# 16_BoardPowerSupply.net
KiCad netlist of a schematic drawn in Altium Designer
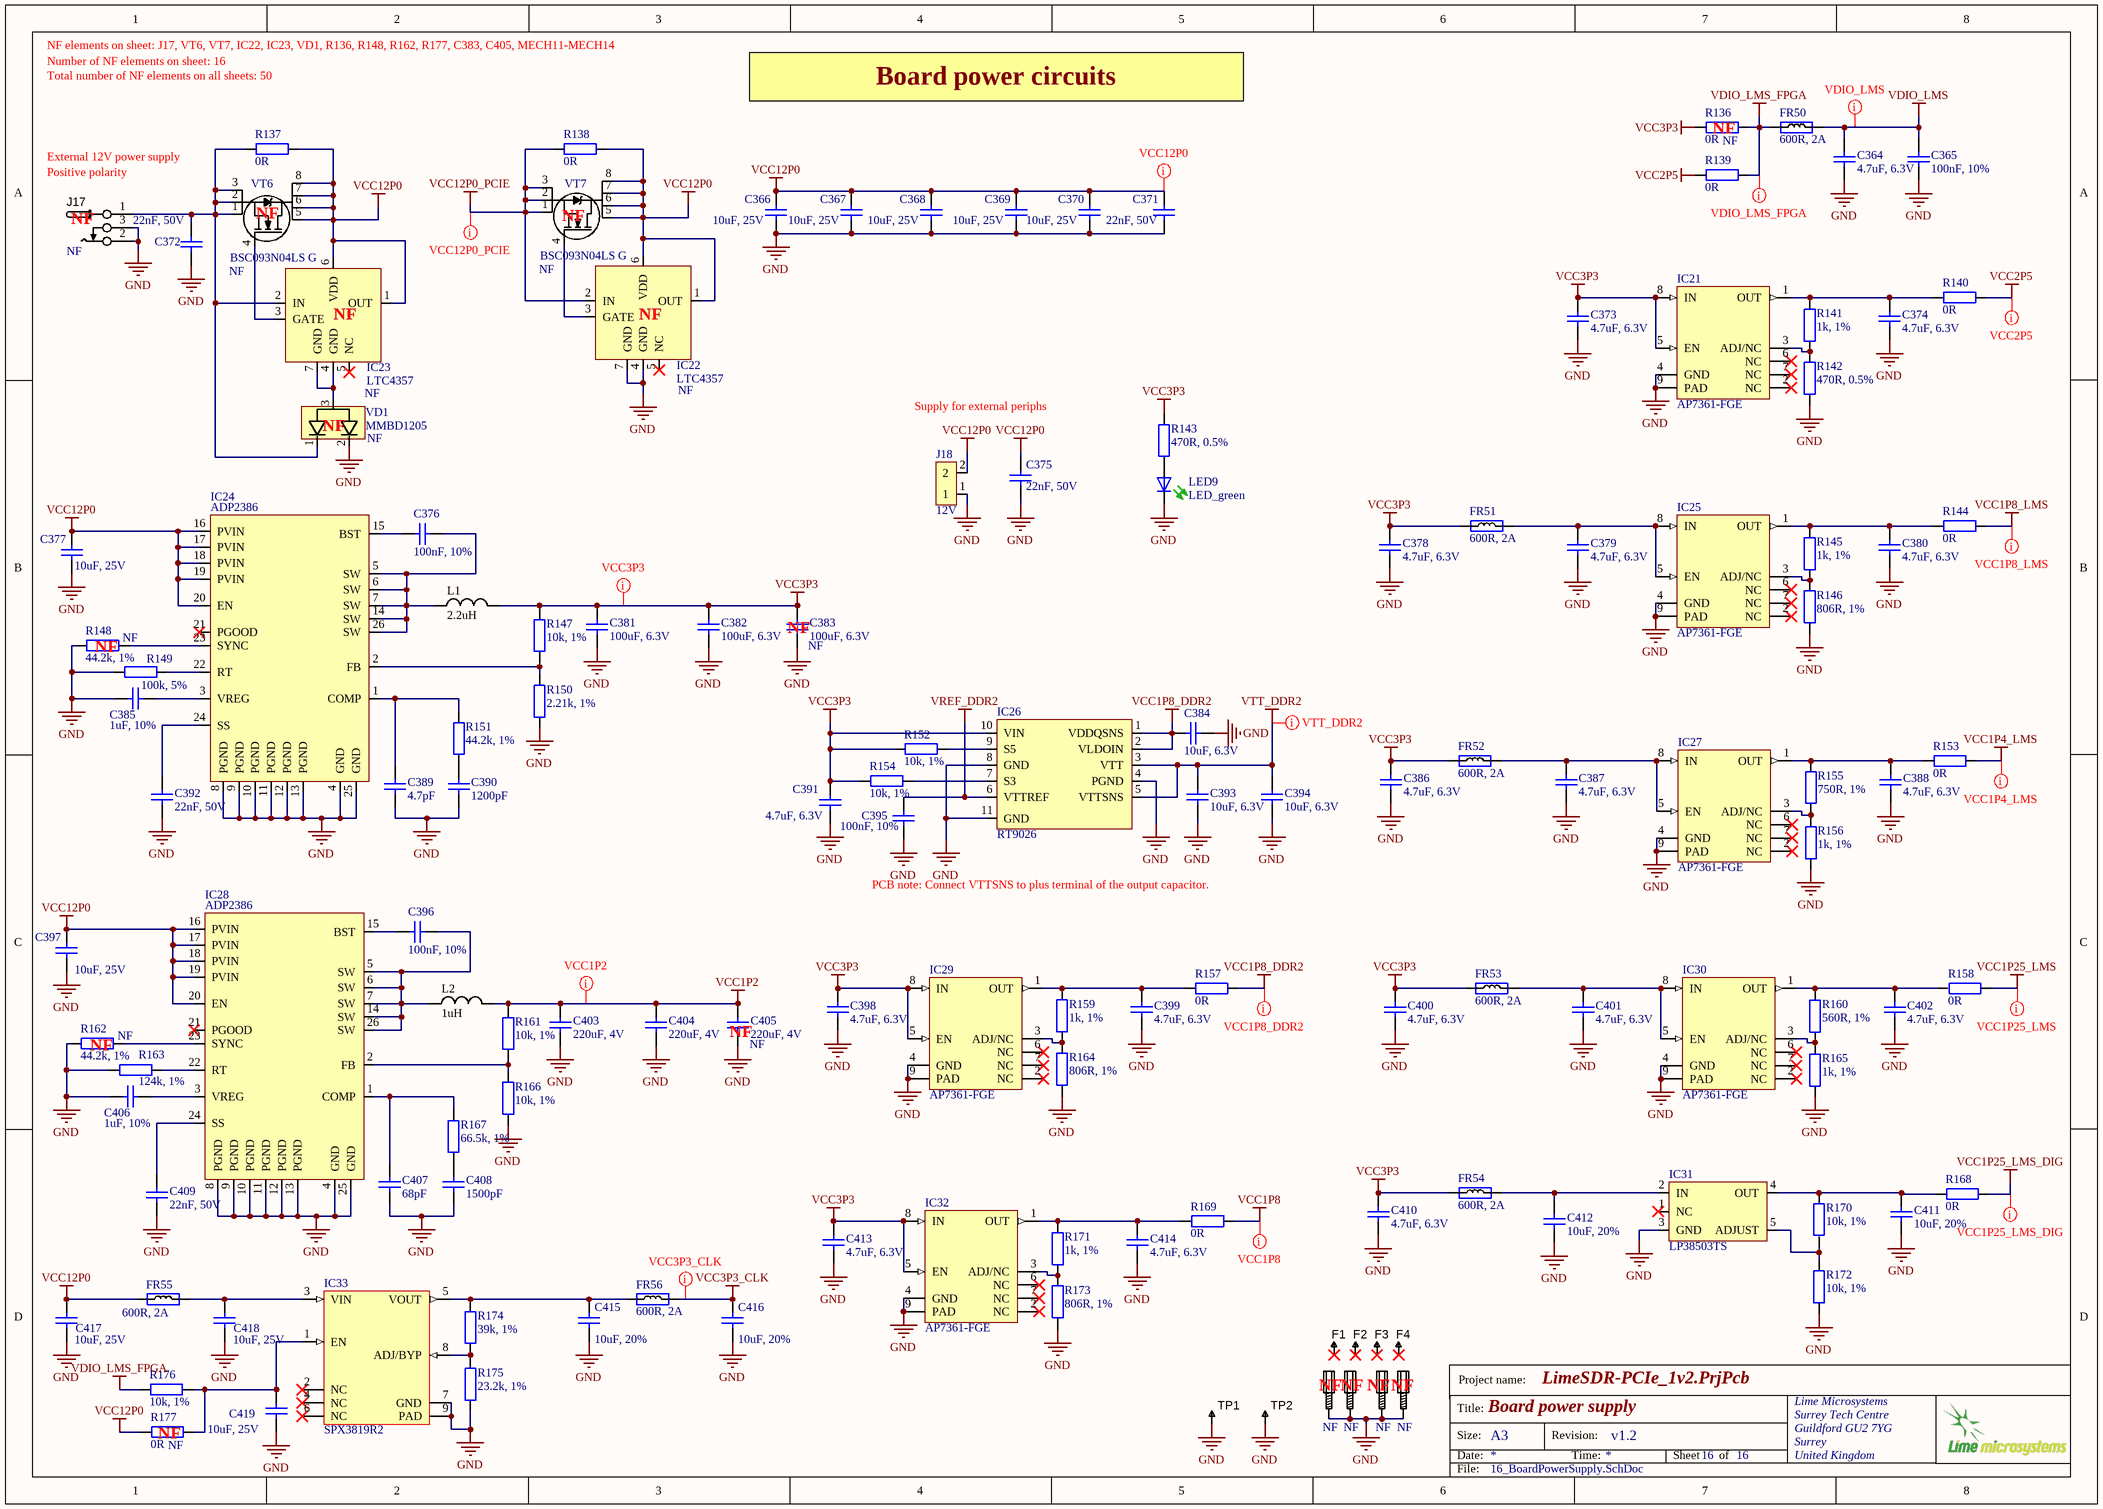
[diagram p0: 16_BoardPowerSupply.SchDoc]

(export (version "E")
  (design (tool "Eeschema 10.0.6"))
  (components
    (comp (ref "C364")
      (value "4.7uF, 6.3V")
      (footprint "CAP0402")
      (fields
        (field (name "MANUFACTURER") "Murata Electronics North America")
        (field (name "TOLERANCE") "±20%")
      )
      (libsource (lib "LimeMicroAltiumLib_schLib") (part "Cap_0402"))
    )
    (comp (ref "C365")
      (value "100nF, 10%")
      (footprint "CAP0402")
      (fields
        (field (name "MANUFACTURER") "Murata Electronics")
        (field (name "TOLERANCE") "10 %")
        (field (name "MANUFACTURER PART NUMBER") "GRM155R71C104KA88D")
      )
      (libsource (lib "LimeMicroAltiumLib_schLib") (part "Cap_0402"))
    )
    (comp (ref "C366")
      (value "10uF, 25V")
      (footprint "CAP0603")
      (fields
        (field (name "MANUFACTURER") "Murata Electronics North America")
        (field (name "MANUFACTURER PART NUMBER") "GRM188R61E106MA73D")
        (field (name "TOLERANCE") "±20%")
      )
      (libsource (lib "LimeMicroAltiumLib_schLib") (part "Cap_0603"))
    )
    (comp (ref "C367")
      (value "10uF, 25V")
      (footprint "CAP0603")
      (fields
        (field (name "MANUFACTURER") "Murata Electronics North America")
        (field (name "MANUFACTURER PART NUMBER") "GRM188R61E106MA73D")
        (field (name "TOLERANCE") "±20%")
      )
      (libsource (lib "LimeMicroAltiumLib_schLib") (part "Cap_0603"))
    )
    (comp (ref "C368")
      (value "10uF, 25V")
      (footprint "CAP0603")
      (fields
        (field (name "MANUFACTURER") "Murata Electronics North America")
        (field (name "MANUFACTURER PART NUMBER") "GRM188R61E106MA73D")
        (field (name "TOLERANCE") "±20%")
      )
      (libsource (lib "LimeMicroAltiumLib_schLib") (part "Cap_0603"))
    )
    (comp (ref "C369")
      (value "10uF, 25V")
      (footprint "CAP0603")
      (fields
        (field (name "MANUFACTURER") "Murata Electronics North America")
        (field (name "MANUFACTURER PART NUMBER") "GRM188R61E106MA73D")
        (field (name "TOLERANCE") "±20%")
      )
      (libsource (lib "LimeMicroAltiumLib_schLib") (part "Cap_0603"))
    )
    (comp (ref "C370")
      (value "10uF, 25V")
      (footprint "CAP0603")
      (fields
        (field (name "MANUFACTURER") "Murata Electronics North America")
        (field (name "MANUFACTURER PART NUMBER") "GRM188R61E106MA73D")
        (field (name "TOLERANCE") "±20%")
      )
      (libsource (lib "LimeMicroAltiumLib_schLib") (part "Cap_0603"))
    )
    (comp (ref "C371")
      (value "22nF, 50V")
      (footprint "CAP0402")
      (fields (field (name "TOLERANCE") "±10%") (field (name "MANUFACTURER") "Kemet"))
      (libsource (lib "LimeMicroAltiumLib_schLib") (part "Cap_0402"))
    )
    (comp (ref "C372")
      (value "22nF, 50V")
      (footprint "CAP0402")
      (fields (field (name "TOLERANCE") "±10%") (field (name "MANUFACTURER") "Kemet"))
      (libsource (lib "LimeMicroAltiumLib_schLib") (part "Cap_0402"))
    )
    (comp (ref "C373")
      (value "4.7uF, 6.3V")
      (footprint "CAP0402")
      (fields
        (field (name "MANUFACTURER") "Murata Electronics North America")
        (field (name "TOLERANCE") "±20%")
      )
      (libsource (lib "LimeMicroAltiumLib_schLib") (part "Cap_0402"))
    )
    (comp (ref "C374")
      (value "4.7uF, 6.3V")
      (footprint "CAP0402")
      (fields
        (field (name "MANUFACTURER") "Murata Electronics North America")
        (field (name "TOLERANCE") "±20%")
      )
      (libsource (lib "LimeMicroAltiumLib_schLib") (part "Cap_0402"))
    )
    (comp (ref "C375")
      (value "22nF, 50V")
      (footprint "CAP0402")
      (fields (field (name "TOLERANCE") "±10%") (field (name "MANUFACTURER") "Kemet"))
      (libsource (lib "LimeMicroAltiumLib_schLib") (part "Cap_0402"))
    )
    (comp (ref "C376")
      (value "100nF, 10%")
      (footprint "CAP0402")
      (fields
        (field (name "MANUFACTURER") "Murata Electronics")
        (field (name "TOLERANCE") "10 %")
        (field (name "MANUFACTURER PART NUMBER") "GRM155R71C104KA88D")
      )
      (libsource (lib "LimeMicroAltiumLib_schLib") (part "Cap_0402"))
    )
    (comp (ref "C377")
      (value "10uF, 25V")
      (footprint "CAP0603")
      (fields
        (field (name "MANUFACTURER") "Murata Electronics North America")
        (field (name "MANUFACTURER PART NUMBER") "GRM188R61E106MA73D")
        (field (name "TOLERANCE") "±20%")
      )
      (libsource (lib "LimeMicroAltiumLib_schLib") (part "Cap_0603"))
    )
    (comp (ref "C378")
      (value "4.7uF, 6.3V")
      (footprint "CAP0402")
      (fields
        (field (name "MANUFACTURER") "Murata Electronics North America")
        (field (name "TOLERANCE") "±20%")
      )
      (libsource (lib "LimeMicroAltiumLib_schLib") (part "Cap_0402"))
    )
    (comp (ref "C379")
      (value "4.7uF, 6.3V")
      (footprint "CAP0402")
      (fields
        (field (name "MANUFACTURER") "Murata Electronics North America")
        (field (name "TOLERANCE") "±20%")
      )
      (libsource (lib "LimeMicroAltiumLib_schLib") (part "Cap_0402"))
    )
    (comp (ref "C380")
      (value "4.7uF, 6.3V")
      (footprint "CAP0402")
      (fields
        (field (name "MANUFACTURER") "Murata Electronics North America")
        (field (name "TOLERANCE") "±20%")
      )
      (libsource (lib "LimeMicroAltiumLib_schLib") (part "Cap_0402"))
    )
    (comp (ref "C381")
      (value "100uF, 6.3V")
      (footprint "CAP1206")
      (fields (field (name "MANUFACTURER") "MURATA"))
      (libsource (lib "LimeFPGAboard_schLib") (part "Cap_1206"))
    )
    (comp (ref "C382")
      (value "100uF, 6.3V")
      (footprint "CAP1206")
      (fields (field (name "MANUFACTURER") "MURATA"))
      (libsource (lib "LimeFPGAboard_schLib") (part "Cap_1206"))
    )
    (comp (ref "C383")
      (value "100uF, 6.3V")
      (footprint "CAP1206")
      (fields (field (name "MANUFACTURER") "MURATA") (field (name "ASSEMBLY INFO") "NF"))
      (libsource (lib "LimeFPGAboard_schLib") (part "Cap_1206"))
    )
    (comp (ref "C384")
      (value "10uF, 6.3V")
      (footprint "CAP0603")
      (fields (field (name "TOLERANCE") "±20%") (field (name "MANUFACTURER") "Yageo"))
      (libsource (lib "LimeFPGAboard_schLib") (part "Cap_0603"))
    )
    (comp (ref "C385")
      (value "1uF, 10%")
      (footprint "CAP0402")
      (fields (field (name "MANUFACTURER") "TDK"))
      (libsource (lib "LimeMicroAltiumLib_schLib") (part "Cap_0402"))
    )
    (comp (ref "C386")
      (value "4.7uF, 6.3V")
      (footprint "CAP0402")
      (fields
        (field (name "MANUFACTURER") "Murata Electronics North America")
        (field (name "TOLERANCE") "±20%")
      )
      (libsource (lib "LimeMicroAltiumLib_schLib") (part "Cap_0402"))
    )
    (comp (ref "C387")
      (value "4.7uF, 6.3V")
      (footprint "CAP0402")
      (fields
        (field (name "MANUFACTURER") "Murata Electronics North America")
        (field (name "TOLERANCE") "±20%")
      )
      (libsource (lib "LimeMicroAltiumLib_schLib") (part "Cap_0402"))
    )
    (comp (ref "C388")
      (value "4.7uF, 6.3V")
      (footprint "CAP0402")
      (fields
        (field (name "MANUFACTURER") "Murata Electronics North America")
        (field (name "TOLERANCE") "±20%")
      )
      (libsource (lib "LimeMicroAltiumLib_schLib") (part "Cap_0402"))
    )
    (comp (ref "C389")
      (value "4.7pF")
      (footprint "CAP0402")
      (fields (field (name "MANUFACTURER") "MURATA"))
      (libsource (lib "LimeMicroAltiumLib_schLib") (part "Cap_0402"))
    )
    (comp (ref "C390")
      (value "1200pF")
      (footprint "CAP0402")
      (fields (field (name "MANUFACTURER") "Kemet") (field (name "TOLERANCE") "±5%"))
      (libsource (lib "LimeMicroAltiumLib_schLib") (part "Cap_0402"))
    )
    (comp (ref "C391")
      (value "4.7uF, 6.3V")
      (footprint "CAP0402")
      (fields
        (field (name "MANUFACTURER") "Murata Electronics North America")
        (field (name "TOLERANCE") "±20%")
      )
      (libsource (lib "LimeMicroAltiumLib_schLib") (part "Cap_0402"))
    )
    (comp (ref "C392")
      (value "22nF, 50V")
      (footprint "CAP0402")
      (fields (field (name "TOLERANCE") "±10%") (field (name "MANUFACTURER") "Kemet"))
      (libsource (lib "LimeMicroAltiumLib_schLib") (part "Cap_0402"))
    )
    (comp (ref "C393")
      (value "10uF, 6.3V")
      (footprint "CAP0603")
      (fields (field (name "TOLERANCE") "±20%") (field (name "MANUFACTURER") "Yageo"))
      (libsource (lib "LimeFPGAboard_schLib") (part "Cap_0603"))
    )
    (comp (ref "C394")
      (value "10uF, 6.3V")
      (footprint "CAP0603")
      (fields (field (name "TOLERANCE") "±20%") (field (name "MANUFACTURER") "Yageo"))
      (libsource (lib "LimeFPGAboard_schLib") (part "Cap_0603"))
    )
    (comp (ref "C395")
      (value "100nF, 10%")
      (footprint "CAP0402")
      (fields
        (field (name "MANUFACTURER") "Murata Electronics")
        (field (name "TOLERANCE") "10 %")
        (field (name "MANUFACTURER PART NUMBER") "GRM155R71C104KA88D")
      )
      (libsource (lib "LimeMicroAltiumLib_schLib") (part "Cap_0402"))
    )
    (comp (ref "C396")
      (value "100nF, 10%")
      (footprint "CAP0402")
      (fields
        (field (name "MANUFACTURER") "Murata Electronics")
        (field (name "TOLERANCE") "10 %")
        (field (name "MANUFACTURER PART NUMBER") "GRM155R71C104KA88D")
      )
      (libsource (lib "LimeMicroAltiumLib_schLib") (part "Cap_0402"))
    )
    (comp (ref "C397")
      (value "10uF, 25V")
      (footprint "CAP0603")
      (fields
        (field (name "MANUFACTURER") "Murata Electronics North America")
        (field (name "MANUFACTURER PART NUMBER") "GRM188R61E106MA73D")
        (field (name "TOLERANCE") "±20%")
      )
      (libsource (lib "LimeMicroAltiumLib_schLib") (part "Cap_0603"))
    )
    (comp (ref "C398")
      (value "4.7uF, 6.3V")
      (footprint "CAP0402")
      (fields
        (field (name "MANUFACTURER") "Murata Electronics North America")
        (field (name "TOLERANCE") "±20%")
      )
      (libsource (lib "LimeMicroAltiumLib_schLib") (part "Cap_0402"))
    )
    (comp (ref "C399")
      (value "4.7uF, 6.3V")
      (footprint "CAP0402")
      (fields
        (field (name "MANUFACTURER") "Murata Electronics North America")
        (field (name "TOLERANCE") "±20%")
      )
      (libsource (lib "LimeMicroAltiumLib_schLib") (part "Cap_0402"))
    )
    (comp (ref "C400")
      (value "4.7uF, 6.3V")
      (footprint "CAP0402")
      (fields
        (field (name "MANUFACTURER") "Murata Electronics North America")
        (field (name "TOLERANCE") "±20%")
      )
      (libsource (lib "LimeMicroAltiumLib_schLib") (part "Cap_0402"))
    )
    (comp (ref "C401")
      (value "4.7uF, 6.3V")
      (footprint "CAP0402")
      (fields
        (field (name "MANUFACTURER") "Murata Electronics North America")
        (field (name "TOLERANCE") "±20%")
      )
      (libsource (lib "LimeMicroAltiumLib_schLib") (part "Cap_0402"))
    )
    (comp (ref "C402")
      (value "4.7uF, 6.3V")
      (footprint "CAP0402")
      (fields
        (field (name "MANUFACTURER") "Murata Electronics North America")
        (field (name "TOLERANCE") "±20%")
      )
      (libsource (lib "LimeMicroAltiumLib_schLib") (part "Cap_0402"))
    )
    (comp (ref "C403")
      (value "220uF, 4V")
      (footprint "CAP1206")
      (fields
        (field (name "MANUFACTURER PART NUMBER") "GRM31CR60G227ME11L")
        (field (name "MANUFACTURER") "Murata Electronics North America")
        (field (name "TOLERANCE") "±20%")
      )
      (libsource (lib "LimeFPGAboard_schLib") (part "Cap_1206"))
    )
    (comp (ref "C404")
      (value "220uF, 4V")
      (footprint "CAP1206")
      (fields
        (field (name "MANUFACTURER PART NUMBER") "GRM31CR60G227ME11L")
        (field (name "MANUFACTURER") "Murata Electronics North America")
        (field (name "TOLERANCE") "±20%")
      )
      (libsource (lib "LimeFPGAboard_schLib") (part "Cap_1206"))
    )
    (comp (ref "C405")
      (value "220uF, 4V")
      (footprint "CAP1206")
      (fields
        (field (name "MANUFACTURER PART NUMBER") "GRM31CR60G227ME11L")
        (field (name "MANUFACTURER") "Murata Electronics North America")
        (field (name "TOLERANCE") "±20%")
        (field (name "ASSEMBLY INFO") "NF")
      )
      (libsource (lib "LimeFPGAboard_schLib") (part "Cap_1206"))
    )
    (comp (ref "C406")
      (value "1uF, 10%")
      (footprint "CAP0402")
      (fields (field (name "MANUFACTURER") "TDK"))
      (libsource (lib "LimeMicroAltiumLib_schLib") (part "Cap_0402"))
    )
    (comp (ref "C407")
      (value "68pF")
      (footprint "CAP0402")
      (fields (field (name "TOLERANCE") "±1%") (field (name "MANUFACTURER") "Kemet"))
      (libsource (lib "LimeMicroAltiumLib_schLib") (part "Cap_0402"))
    )
    (comp (ref "C408")
      (value "1500pF")
      (footprint "CAP0402")
      (fields
        (field (name "MANUFACTURER") "Samsung Electro-Mechanics America, Inc.")
        (field (name "TOLERANCE") "±10%")
      )
      (libsource (lib "LimeMicroAltiumLib_schLib") (part "Cap_0402"))
    )
    (comp (ref "C409")
      (value "22nF, 50V")
      (footprint "CAP0402")
      (fields (field (name "TOLERANCE") "±10%") (field (name "MANUFACTURER") "Kemet"))
      (libsource (lib "LimeMicroAltiumLib_schLib") (part "Cap_0402"))
    )
    (comp (ref "C410")
      (value "4.7uF, 6.3V")
      (footprint "CAP0402")
      (fields
        (field (name "MANUFACTURER") "Murata Electronics North America")
        (field (name "TOLERANCE") "±20%")
      )
      (libsource (lib "LimeMicroAltiumLib_schLib") (part "Cap_0402"))
    )
    (comp (ref "C411")
      (value "10uF, 20%")
      (footprint "CAP0603")
      (fields (field (name "MANUFACTURER") "Yageo") (field (name "TOLERANCE") "±20%"))
      (libsource (lib "LimeMicroAltiumLib_schLib") (part "Cap_0603"))
    )
    (comp (ref "C412")
      (value "10uF, 20%")
      (footprint "CAP0603")
      (fields (field (name "MANUFACTURER") "Yageo") (field (name "TOLERANCE") "±20%"))
      (libsource (lib "LimeMicroAltiumLib_schLib") (part "Cap_0603"))
    )
    (comp (ref "C413")
      (value "4.7uF, 6.3V")
      (footprint "CAP0402")
      (fields
        (field (name "MANUFACTURER") "Murata Electronics North America")
        (field (name "TOLERANCE") "±20%")
      )
      (libsource (lib "LimeMicroAltiumLib_schLib") (part "Cap_0402"))
    )
    (comp (ref "C414")
      (value "4.7uF, 6.3V")
      (footprint "CAP0402")
      (fields
        (field (name "MANUFACTURER") "Murata Electronics North America")
        (field (name "TOLERANCE") "±20%")
      )
      (libsource (lib "LimeMicroAltiumLib_schLib") (part "Cap_0402"))
    )
    (comp (ref "C415")
      (value "10uF, 20%")
      (footprint "CAP0603")
      (fields (field (name "MANUFACTURER") "Yageo") (field (name "TOLERANCE") "±20%"))
      (libsource (lib "LimeMicroAltiumLib_schLib") (part "Cap_0603"))
    )
    (comp (ref "C416")
      (value "10uF, 20%")
      (footprint "CAP0603")
      (fields (field (name "MANUFACTURER") "Yageo") (field (name "TOLERANCE") "±20%"))
      (libsource (lib "LimeMicroAltiumLib_schLib") (part "Cap_0603"))
    )
    (comp (ref "C417")
      (value "10uF, 25V")
      (footprint "CAP0603")
      (fields
        (field (name "MANUFACTURER") "Murata Electronics North America")
        (field (name "MANUFACTURER PART NUMBER") "GRM188R61E106MA73D")
        (field (name "TOLERANCE") "±20%")
      )
      (libsource (lib "LimeMicroAltiumLib_schLib") (part "Cap_0603"))
    )
    (comp (ref "C418")
      (value "10uF, 25V")
      (footprint "CAP0603")
      (fields
        (field (name "MANUFACTURER") "Murata Electronics North America")
        (field (name "MANUFACTURER PART NUMBER") "GRM188R61E106MA73D")
        (field (name "TOLERANCE") "±20%")
      )
      (libsource (lib "LimeMicroAltiumLib_schLib") (part "Cap_0603"))
    )
    (comp (ref "C419")
      (value "10uF, 25V")
      (footprint "CAP0603")
      (fields
        (field (name "MANUFACTURER") "Murata Electronics North America")
        (field (name "MANUFACTURER PART NUMBER") "GRM188R61E106MA73D")
        (field (name "TOLERANCE") "±20%")
      )
      (libsource (lib "LimeMicroAltiumLib_schLib") (part "Cap_0603"))
    )
    (comp (ref "F1")
      (value "Fiducial")
      (footprint "Fiducial")
      (libsource (lib "LimeMicroAltiumLib_schLib") (part "Fiducial"))
    )
    (comp (ref "F2")
      (value "Fiducial")
      (footprint "Fiducial")
      (libsource (lib "LimeMicroAltiumLib_schLib") (part "Fiducial"))
    )
    (comp (ref "F3")
      (value "Fiducial")
      (footprint "Fiducial")
      (libsource (lib "LimeMicroAltiumLib_schLib") (part "Fiducial"))
    )
    (comp (ref "F4")
      (value "Fiducial")
      (footprint "Fiducial")
      (libsource (lib "LimeMicroAltiumLib_schLib") (part "Fiducial"))
    )
    (comp (ref "FR50")
      (value "600R, 2A")
      (footprint "RES0805")
      (fields (field (name "MANUFACTURER") "TDK Corporation"))
      (libsource (lib "LimeMicroAltiumLib_schLib") (part "Ferrite"))
    )
    (comp (ref "FR51")
      (value "600R, 2A")
      (footprint "RES0805")
      (fields (field (name "MANUFACTURER") "TDK Corporation"))
      (libsource (lib "LimeMicroAltiumLib_schLib") (part "Ferrite"))
    )
    (comp (ref "FR52")
      (value "600R, 2A")
      (footprint "RES0805")
      (fields (field (name "MANUFACTURER") "TDK Corporation"))
      (libsource (lib "LimeMicroAltiumLib_schLib") (part "Ferrite"))
    )
    (comp (ref "FR53")
      (value "600R, 2A")
      (footprint "RES0805")
      (fields (field (name "MANUFACTURER") "TDK Corporation"))
      (libsource (lib "LimeMicroAltiumLib_schLib") (part "Ferrite"))
    )
    (comp (ref "FR54")
      (value "600R, 2A")
      (footprint "RES0805")
      (fields (field (name "MANUFACTURER") "TDK Corporation"))
      (libsource (lib "LimeMicroAltiumLib_schLib") (part "Ferrite"))
    )
    (comp (ref "FR55")
      (value "600R, 2A")
      (footprint "RES0805")
      (fields (field (name "MANUFACTURER") "TDK Corporation"))
      (libsource (lib "LimeMicroAltiumLib_schLib") (part "Ferrite"))
    )
    (comp (ref "FR56")
      (value "600R, 2A")
      (footprint "RES0805")
      (fields (field (name "MANUFACTURER") "TDK Corporation"))
      (libsource (lib "LimeMicroAltiumLib_schLib") (part "Ferrite"))
    )
    (comp (ref "IC21")
      (value "AP7361-FGE")
      (footprint "AP7361")
      (fields
        (field (name "MANUFACTURER PART NUMBER") "AP7361-FGE-7")
        (field (name "MANUFACTURER") "Diodes Incorporated")
      )
      (libsource (lib "LimeMicroAltiumLib_schLib") (part "AP7361"))
    )
    (comp (ref "IC22")
      (value "LTC4357")
      (footprint "LTC4357")
      (fields
        (field (name "MANUFACTURER PART NUMBER") "LTC4357IDCB#TRMPBF")
        (field (name "MANUFACTURER") "Linear Technology")
        (field (name "ASSEMBLY INFO") "NF")
      )
      (libsource (lib "LimeFPGAboard_schLib") (part "LTC4357"))
    )
    (comp (ref "IC23")
      (value "LTC4357")
      (footprint "LTC4357")
      (fields
        (field (name "MANUFACTURER PART NUMBER") "LTC4357IDCB#TRMPBF")
        (field (name "MANUFACTURER") "Linear Technology")
        (field (name "ASSEMBLY INFO") "NF")
      )
      (libsource (lib "LimeFPGAboard_schLib") (part "LTC4357"))
    )
    (comp (ref "IC24")
      (value "ADP2386")
      (footprint "ADP2386")
      (fields
        (field (name "MANUFACTURER PART NUMBER") "ADP2386ACPZN-R7")
        (field (name "MANUFACTURER") "Analog Devices Inc.")
      )
      (libsource (lib "LimeMicroAltiumLib_schLib") (part "ADP2386"))
    )
    (comp (ref "IC25")
      (value "AP7361-FGE")
      (footprint "AP7361")
      (fields
        (field (name "MANUFACTURER PART NUMBER") "AP7361-FGE-7")
        (field (name "MANUFACTURER") "Diodes Incorporated")
      )
      (libsource (lib "LimeMicroAltiumLib_schLib") (part "AP7361"))
    )
    (comp (ref "IC26")
      (value "RT9026")
      (footprint "MSOP10")
      (fields (field (name "MANUFACTURER") "Richtek USA Inc."))
      (libsource (lib "LimeMicroAltiumLib_schLib") (part "RT9026"))
    )
    (comp (ref "IC27")
      (value "AP7361-FGE")
      (footprint "AP7361")
      (fields
        (field (name "MANUFACTURER PART NUMBER") "AP7361-FGE-7")
        (field (name "MANUFACTURER") "Diodes Incorporated")
      )
      (libsource (lib "LimeMicroAltiumLib_schLib") (part "AP7361"))
    )
    (comp (ref "IC28")
      (value "ADP2386")
      (footprint "ADP2386")
      (fields (field (name "MANUFACTURER") "Analog Devices Inc."))
      (libsource (lib "LimeMicroAltiumLib_schLib") (part "ADP2386"))
    )
    (comp (ref "IC29")
      (value "AP7361-FGE")
      (footprint "AP7361")
      (fields
        (field (name "MANUFACTURER PART NUMBER") "AP7361-FGE-7")
        (field (name "MANUFACTURER") "Diodes Incorporated")
      )
      (libsource (lib "LimeMicroAltiumLib_schLib") (part "AP7361"))
    )
    (comp (ref "IC30")
      (value "AP7361-FGE")
      (footprint "AP7361")
      (fields
        (field (name "MANUFACTURER PART NUMBER") "AP7361-FGE-7")
        (field (name "MANUFACTURER") "Diodes Incorporated")
      )
      (libsource (lib "LimeMicroAltiumLib_schLib") (part "AP7361"))
    )
    (comp (ref "IC31")
      (value "LP38503TS")
      (footprint "TO-263-5_v2")
      (fields
        (field (name "MANUFACTURER PART NUMBER") "LP38503TS-ADJ/NOPB")
        (field (name "MANUFACTURER") "Texas Instruments")
      )
      (libsource (lib "LimeMicroAltiumLib_schLib") (part "LP38503TS"))
    )
    (comp (ref "IC32")
      (value "AP7361-FGE")
      (footprint "AP7361")
      (fields
        (field (name "MANUFACTURER PART NUMBER") "AP7361-FGE-7")
        (field (name "MANUFACTURER") "Diodes Incorporated")
      )
      (libsource (lib "LimeMicroAltiumLib_schLib") (part "AP7361"))
    )
    (comp (ref "IC33")
      (value "SPX3819R2")
      (footprint "SPX3819R2-L/TR")
      (fields (field (name "MANUFACTURER") "Exar Corporation"))
      (libsource (lib "LimeMicroAltiumLib_schLib") (part "SPX3819R2-L/TR"))
    )
    (comp (ref "J17")
      (value "CONN_PWR_JACK_2.1x5.5mm")
      (footprint "CONN_PWR_JACK_v2")
      (description "Power Connector, THT, 2.1mm ID, 5.5mm OD")
      (fields (field (name "MANUFACTURER") "SWITCHCRAFT") (field (name "ASSEMBLY INFO") "NF"))
      (libsource (lib "LimeFPGAboard_schLib") (part "CONN_PWR_JACK_2.1x5.5mm"))
    )
    (comp (ref "J18")
      (value "12V")
      (footprint "HDR_1x2")
      (fields (field (name "MANUFACTURER") "3M"))
      (libsource (lib "LimeFPGAboard_schLib") (part "Jumper"))
    )
    (comp (ref "L1")
      (value "2.2uH")
      (footprint "FDVE1040_TOKO_INDUCTOR")
      (fields (field (name "TOLERANCE") "±20%") (field (name "MANUFACTURER") "Vishay Dale"))
      (libsource (lib "LimeMicroAltiumLib_schLib") (part "Inductor_0603"))
    )
    (comp (ref "L2")
      (value "1uH")
      (footprint "FDVE1040_TOKO_INDUCTOR")
      (fields (field (name "TOLERANCE") "±20%") (field (name "MANUFACTURER") "Vishay Dale"))
      (libsource (lib "LimeMicroAltiumLib_schLib") (part "Inductor_0603"))
    )
    (comp (ref "LED9")
      (value "LED_green")
      (footprint "LED-0603-GREEN")
      (fields (field (name "MANUFACTURER") "Broadcom Limited"))
      (libsource (lib "LimeFPGAboard_schLib") (part "LED_green"))
    )
    (comp (ref "MECH11")
      (value "# pcs.")
      (footprint "PCB_standoff")
      (description "STANDOFF M/F MET 5MM HEX 10MM L")
      (fields (field (name "MANUFACTURER") "Keystone Electronics") (field (name "ASSEMBLY INFO") "NF"))
      (libsource (lib "LimeMicroAltiumLib_schLib") (part "STANDOFF_M-F_THREADED_M3x8x10mm_HEX_5mm dia"))
    )
    (comp (ref "MECH12")
      (value "# pcs.")
      (footprint "PCB_standoff")
      (description "STANDOFF M/F MET 5MM HEX 10MM L")
      (fields (field (name "MANUFACTURER") "Keystone Electronics") (field (name "ASSEMBLY INFO") "NF"))
      (libsource (lib "LimeMicroAltiumLib_schLib") (part "STANDOFF_M-F_THREADED_M3x8x10mm_HEX_5mm dia"))
    )
    (comp (ref "MECH13")
      (value "# pcs.")
      (footprint "PCB_standoff")
      (description "STANDOFF M/F MET 5MM HEX 10MM L")
      (fields (field (name "MANUFACTURER") "Keystone Electronics") (field (name "ASSEMBLY INFO") "NF"))
      (libsource (lib "LimeMicroAltiumLib_schLib") (part "STANDOFF_M-F_THREADED_M3x8x10mm_HEX_5mm dia"))
    )
    (comp (ref "MECH14")
      (value "# pcs.")
      (footprint "PCB_standoff")
      (description "STANDOFF M/F MET 5MM HEX 10MM L")
      (fields (field (name "MANUFACTURER") "Keystone Electronics") (field (name "ASSEMBLY INFO") "NF"))
      (libsource (lib "LimeMicroAltiumLib_schLib") (part "STANDOFF_M-F_THREADED_M3x8x10mm_HEX_5mm dia"))
    )
    (comp (ref "R136")
      (value "0R")
      (footprint "RES0402")
      (fields
        (field (name "ASSEMBLY INFO") "NF")
        (field (name "MANUFACTURER") "Yageo")
        (field (name "TOLERANCE") "Jumper")
      )
      (libsource (lib "LimeMicroAltiumLib_schLib") (part "Res_0402"))
    )
    (comp (ref "R137")
      (value "0R")
      (footprint "RES0805")
      (fields (field (name "MANUFACTURER") "Vishay Dale") (field (name "TOLERANCE") "Jumper"))
      (libsource (lib "LimeMicroAltiumLib_schLib") (part "Res_0402"))
    )
    (comp (ref "R138")
      (value "0R")
      (footprint "RES0805")
      (fields (field (name "MANUFACTURER") "Vishay Dale") (field (name "TOLERANCE") "Jumper"))
      (libsource (lib "LimeMicroAltiumLib_schLib") (part "Res_0402"))
    )
    (comp (ref "R139")
      (value "0R")
      (footprint "RES0402")
      (fields (field (name "MANUFACTURER") "Yageo") (field (name "TOLERANCE") "Jumper"))
      (libsource (lib "LimeMicroAltiumLib_schLib") (part "Res_0402"))
    )
    (comp (ref "R140")
      (value "0R")
      (footprint "RES0402")
      (fields (field (name "MANUFACTURER") "Yageo") (field (name "TOLERANCE") "Jumper"))
      (libsource (lib "LimeMicroAltiumLib_schLib") (part "Res_0402"))
    )
    (comp (ref "R141")
      (value "1k, 1%")
      (footprint "RES0402")
      (fields (field (name "MANUFACTURER") "Stackpole Electronics Inc") (field (name "TOLERANCE") "±1%"))
      (libsource (lib "LimeMicroAltiumLib_schLib") (part "Res_0402"))
    )
    (comp (ref "R142")
      (value "470R, 0.5%")
      (footprint "RES0402")
      (fields
        (field (name "TOLERANCE") "±0.5%")
        (field (name "MANUFACTURER") "Panasonic Electronic Components")
      )
      (libsource (lib "LimeMicroAltiumLib_schLib") (part "Res_0402"))
    )
    (comp (ref "R143")
      (value "470R, 0.5%")
      (footprint "RES0402")
      (fields (field (name "TOLERANCE") "±0.5%"))
      (libsource (lib "LimeFPGAboard_schLib") (part "Res_0402"))
    )
    (comp (ref "R144")
      (value "0R")
      (footprint "RES0402")
      (fields (field (name "MANUFACTURER") "Yageo") (field (name "TOLERANCE") "Jumper"))
      (libsource (lib "LimeMicroAltiumLib_schLib") (part "Res_0402"))
    )
    (comp (ref "R145")
      (value "1k, 1%")
      (footprint "RES0402")
      (fields (field (name "MANUFACTURER") "Stackpole Electronics Inc") (field (name "TOLERANCE") "±1%"))
      (libsource (lib "LimeMicroAltiumLib_schLib") (part "Res_0402"))
    )
    (comp (ref "R146")
      (value "806R, 1%")
      (footprint "RES0402")
      (fields (field (name "TOLERANCE") "±1%") (field (name "MANUFACTURER") "Stackpole Electronics Inc"))
      (libsource (lib "LimeMicroAltiumLib_schLib") (part "Res_0402"))
    )
    (comp (ref "R147")
      (value "10k, 1%")
      (footprint "RES0402")
      (fields (field (name "MANUFACTURER") "Yageo") (field (name "TOLERANCE") "±1%"))
      (libsource (lib "LimeMicroAltiumLib_schLib") (part "Res_0402"))
    )
    (comp (ref "R148")
      (value "44.2k, 1%")
      (footprint "RES0402")
      (fields
        (field (name "ASSEMBLY INFO") "NF")
        (field (name "TOLERANCE") "±1%")
        (field (name "MANUFACTURER") "Panasonic Electronic Components")
      )
      (libsource (lib "LimeMicroAltiumLib_schLib") (part "Res_0402"))
    )
    (comp (ref "R149")
      (value "100k, 5%")
      (footprint "RES0402")
      (fields
        (field (name "MANUFACTURER") "Panasonic Electronic Components")
        (field (name "MANUFACTURER PART NUMBER") "ERJ-2GEJ104X")
        (field (name "TOLERANCE") "±5%")
      )
      (libsource (lib "LimeMicroAltiumLib_schLib") (part "Res_0402"))
    )
    (comp (ref "R150")
      (value "2.21k, 1%")
      (footprint "RES0402")
      (fields (field (name "MANUFACTURER") "Stackpole Electronics Inc.") (field (name "TOLERANCE") "±1%"))
      (libsource (lib "LimeMicroAltiumLib_schLib") (part "Res_0402"))
    )
    (comp (ref "R151")
      (value "44.2k, 1%")
      (footprint "RES0402")
      (fields
        (field (name "TOLERANCE") "±1%")
        (field (name "MANUFACTURER") "Panasonic Electronic Components")
      )
      (libsource (lib "LimeMicroAltiumLib_schLib") (part "Res_0402"))
    )
    (comp (ref "R152")
      (value "10k, 1%")
      (footprint "RES0402")
      (fields (field (name "MANUFACTURER") "Yageo") (field (name "TOLERANCE") "±1%"))
      (libsource (lib "LimeMicroAltiumLib_schLib") (part "Res_0402"))
    )
    (comp (ref "R153")
      (value "0R")
      (footprint "RES0402")
      (fields (field (name "MANUFACTURER") "Yageo") (field (name "TOLERANCE") "Jumper"))
      (libsource (lib "LimeMicroAltiumLib_schLib") (part "Res_0402"))
    )
    (comp (ref "R154")
      (value "10k, 1%")
      (footprint "RES0402")
      (fields (field (name "MANUFACTURER") "Yageo") (field (name "TOLERANCE") "±1%"))
      (libsource (lib "LimeMicroAltiumLib_schLib") (part "Res_0402"))
    )
    (comp (ref "R155")
      (value "750R, 1%")
      (footprint "RES0402")
      (fields
        (field (name "TOLERANCE") "±1%")
        (field (name "MANUFACTURER PART NUMBER") "RC0402FR-07750RL")
        (field (name "MANUFACTURER") "Yageo")
      )
      (libsource (lib "LimeMicroAltiumLib_schLib") (part "Res_0402"))
    )
    (comp (ref "R156")
      (value "1k, 1%")
      (footprint "RES0402")
      (fields (field (name "MANUFACTURER") "Stackpole Electronics Inc") (field (name "TOLERANCE") "±1%"))
      (libsource (lib "LimeMicroAltiumLib_schLib") (part "Res_0402"))
    )
    (comp (ref "R157")
      (value "0R")
      (footprint "RES0402")
      (fields (field (name "MANUFACTURER") "Yageo") (field (name "TOLERANCE") "Jumper"))
      (libsource (lib "LimeMicroAltiumLib_schLib") (part "Res_0402"))
    )
    (comp (ref "R158")
      (value "0R")
      (footprint "RES0402")
      (fields (field (name "MANUFACTURER") "Yageo") (field (name "TOLERANCE") "Jumper"))
      (libsource (lib "LimeMicroAltiumLib_schLib") (part "Res_0402"))
    )
    (comp (ref "R159")
      (value "1k, 1%")
      (footprint "RES0402")
      (fields (field (name "MANUFACTURER") "Stackpole Electronics Inc") (field (name "TOLERANCE") "±1%"))
      (libsource (lib "LimeMicroAltiumLib_schLib") (part "Res_0402"))
    )
    (comp (ref "R160")
      (value "560R, 1%")
      (footprint "RES0402")
      (fields
        (field (name "MANUFACTURER PART NUMBER") "CRCW0402560RFKED")
        (field (name "TOLERANCE") "±1%")
        (field (name "MANUFACTURER") "Vishay Dale")
      )
      (libsource (lib "LimeMicroAltiumLib_schLib") (part "Res_0402"))
    )
    (comp (ref "R161")
      (value "10k, 1%")
      (footprint "RES0402")
      (fields (field (name "MANUFACTURER") "Yageo") (field (name "TOLERANCE") "±1%"))
      (libsource (lib "LimeMicroAltiumLib_schLib") (part "Res_0402"))
    )
    (comp (ref "R162")
      (value "44.2k, 1%")
      (footprint "RES0402")
      (fields
        (field (name "ASSEMBLY INFO") "NF")
        (field (name "TOLERANCE") "±1%")
        (field (name "MANUFACTURER") "Panasonic Electronic Components")
      )
      (libsource (lib "LimeMicroAltiumLib_schLib") (part "Res_0402"))
    )
    (comp (ref "R163")
      (value "124k, 1%")
      (footprint "RES0402")
      (fields
        (field (name "MANUFACTURER") "Panasonic Electronic Components")
        (field (name "TOLERANCE") "±1%")
      )
      (libsource (lib "LimeMicroAltiumLib_schLib") (part "Res_0402"))
    )
    (comp (ref "R164")
      (value "806R, 1%")
      (footprint "RES0402")
      (fields (field (name "TOLERANCE") "±1%") (field (name "MANUFACTURER") "Stackpole Electronics Inc"))
      (libsource (lib "LimeMicroAltiumLib_schLib") (part "Res_0402"))
    )
    (comp (ref "R165")
      (value "1k, 1%")
      (footprint "RES0402")
      (fields (field (name "MANUFACTURER") "Stackpole Electronics Inc") (field (name "TOLERANCE") "±1%"))
      (libsource (lib "LimeMicroAltiumLib_schLib") (part "Res_0402"))
    )
    (comp (ref "R166")
      (value "10k, 1%")
      (footprint "RES0402")
      (fields (field (name "MANUFACTURER") "Yageo") (field (name "TOLERANCE") "±1%"))
      (libsource (lib "LimeMicroAltiumLib_schLib") (part "Res_0402"))
    )
    (comp (ref "R167")
      (value "66.5k, 1%")
      (footprint "RES0402")
      (fields
        (field (name "MANUFACTURER") "Panasonic Electronic Components")
        (field (name "TOLERANCE") "±1%")
      )
      (libsource (lib "LimeMicroAltiumLib_schLib") (part "Res_0402"))
    )
    (comp (ref "R168")
      (value "0R")
      (footprint "RES0402")
      (fields (field (name "MANUFACTURER") "Yageo") (field (name "TOLERANCE") "Jumper"))
      (libsource (lib "LimeMicroAltiumLib_schLib") (part "Res_0402"))
    )
    (comp (ref "R169")
      (value "0R")
      (footprint "RES0402")
      (fields (field (name "MANUFACTURER") "Yageo") (field (name "TOLERANCE") "Jumper"))
      (libsource (lib "LimeMicroAltiumLib_schLib") (part "Res_0402"))
    )
    (comp (ref "R170")
      (value "10k, 1%")
      (footprint "RES0402")
      (fields (field (name "MANUFACTURER") "Yageo") (field (name "TOLERANCE") "±1%"))
      (libsource (lib "LimeMicroAltiumLib_schLib") (part "Res_0402"))
    )
    (comp (ref "R171")
      (value "1k, 1%")
      (footprint "RES0402")
      (fields (field (name "MANUFACTURER") "Stackpole Electronics Inc") (field (name "TOLERANCE") "±1%"))
      (libsource (lib "LimeMicroAltiumLib_schLib") (part "Res_0402"))
    )
    (comp (ref "R172")
      (value "10k, 1%")
      (footprint "RES0402")
      (fields (field (name "MANUFACTURER") "Yageo") (field (name "TOLERANCE") "±1%"))
      (libsource (lib "LimeMicroAltiumLib_schLib") (part "Res_0402"))
    )
    (comp (ref "R173")
      (value "806R, 1%")
      (footprint "RES0402")
      (fields (field (name "TOLERANCE") "±1%") (field (name "MANUFACTURER") "Stackpole Electronics Inc"))
      (libsource (lib "LimeMicroAltiumLib_schLib") (part "Res_0402"))
    )
    (comp (ref "R174")
      (value "39k, 1%")
      (footprint "RES0402")
      (fields (field (name "MANUFACTURER") "Yageo") (field (name "TOLERANCE") "±1%"))
      (libsource (lib "LimeMicroAltiumLib_schLib") (part "Res_0402"))
    )
    (comp (ref "R175")
      (value "23.2k, 1%")
      (footprint "RES0402")
      (fields (field (name "TOLERANCE") "±1%") (field (name "MANUFACTURER") "Yageo"))
      (libsource (lib "LimeMicroAltiumLib_schLib") (part "Res_0402"))
    )
    (comp (ref "R176")
      (value "10k, 1%")
      (footprint "RES0402")
      (fields (field (name "MANUFACTURER") "Yageo") (field (name "TOLERANCE") "±1%"))
      (libsource (lib "LimeMicroAltiumLib_schLib") (part "Res_0402"))
    )
    (comp (ref "R177")
      (value "0R")
      (footprint "RES0402")
      (fields
        (field (name "ASSEMBLY INFO") "NF")
        (field (name "MANUFACTURER") "Yageo")
        (field (name "TOLERANCE") "Jumper")
      )
      (libsource (lib "LimeMicroAltiumLib_schLib") (part "Res_0402"))
    )
    (comp (ref "TP1")
      (value "TESTPOINT_THT_MINI")
      (footprint "TP-THT-MIDI")
      (description "Test Point PCB mount Miniature White")
      (fields (field (name "MANUFACTURER") "Keystone Electronics"))
      (libsource (lib "LimeMicroAltiumLib_schLib") (part "TESTPOINT_THT_MINI"))
    )
    (comp (ref "TP2")
      (value "TESTPOINT_THT_MINI")
      (footprint "TP-THT-MIDI")
      (description "Test Point PCB mount Miniature White")
      (fields (field (name "MANUFACTURER") "Keystone Electronics"))
      (libsource (lib "LimeMicroAltiumLib_schLib") (part "TESTPOINT_THT_MINI"))
    )
    (comp (ref "VD1")
      (value "MMBD1205")
      (footprint "SOT23-3_v2")
      (fields (field (name "MANUFACTURER") "FAIRCHILD SEMICONDUCTOR") (field (name "ASSEMBLY INFO") "NF"))
      (libsource (lib "LimeFPGAboard_schLib") (part "MMBD1205"))
    )
    (comp (ref "VT6")
      (value "BSC093N04LS G")
      (footprint "BSC093N04LS_G")
      (fields (field (name "MANUFACTURER") "Infineon Technologies") (field (name "ASSEMBLY INFO") "NF"))
      (libsource (lib "LimeFPGAboard_schLib") (part "BSC093N04LS_G"))
    )
    (comp (ref "VT7")
      (value "BSC093N04LS G")
      (footprint "BSC093N04LS_G")
      (fields (field (name "MANUFACTURER") "Infineon Technologies") (field (name "ASSEMBLY INFO") "NF"))
      (libsource (lib "LimeFPGAboard_schLib") (part "BSC093N04LS_G"))
    )
  )
  (nets
    (net (code "1") (name "GND") (class "Default")
      (node (ref "C364") (pin "1") (pinfunction "1_1") (pintype "passive"))
      (node (ref "C365") (pin "2") (pinfunction "2_2") (pintype "passive"))
      (node (ref "C366") (pin "1") (pinfunction "1_1") (pintype "passive"))
      (node (ref "C367") (pin "1") (pinfunction "1_1") (pintype "passive"))
      (node (ref "C368") (pin "1") (pinfunction "1_1") (pintype "passive"))
      (node (ref "C369") (pin "1") (pinfunction "1_1") (pintype "passive"))
      (node (ref "C370") (pin "1") (pinfunction "1_1") (pintype "passive"))
      (node (ref "C371") (pin "2") (pinfunction "2_2") (pintype "passive"))
      (node (ref "C372") (pin "2") (pinfunction "2_2") (pintype "passive"))
      (node (ref "C373") (pin "1") (pinfunction "1_1") (pintype "passive"))
      (node (ref "C374") (pin "1") (pinfunction "1_1") (pintype "passive"))
      (node (ref "C375") (pin "2") (pinfunction "2_2") (pintype "passive"))
      (node (ref "C377") (pin "1") (pinfunction "1_1") (pintype "passive"))
      (node (ref "C378") (pin "1") (pinfunction "1_1") (pintype "passive"))
      (node (ref "C379") (pin "1") (pinfunction "1_1") (pintype "passive"))
      (node (ref "C380") (pin "1") (pinfunction "1_1") (pintype "passive"))
      (node (ref "C381") (pin "1") (pinfunction "1_1") (pintype "passive"))
      (node (ref "C382") (pin "1") (pinfunction "1_1") (pintype "passive"))
      (node (ref "C383") (pin "1") (pinfunction "1_1") (pintype "passive"))
      (node (ref "C384") (pin "1") (pinfunction "1_1") (pintype "passive"))
      (node (ref "C385") (pin "2") (pinfunction "2_2") (pintype "passive"))
      (node (ref "C386") (pin "1") (pinfunction "1_1") (pintype "passive"))
      (node (ref "C387") (pin "1") (pinfunction "1_1") (pintype "passive"))
      (node (ref "C388") (pin "1") (pinfunction "1_1") (pintype "passive"))
      (node (ref "C389") (pin "2") (pinfunction "2_2") (pintype "passive"))
      (node (ref "C390") (pin "2") (pinfunction "2_2") (pintype "passive"))
      (node (ref "C391") (pin "1") (pinfunction "1_1") (pintype "passive"))
      (node (ref "C392") (pin "2") (pinfunction "2_2") (pintype "passive"))
      (node (ref "C393") (pin "1") (pinfunction "1_1") (pintype "passive"))
      (node (ref "C394") (pin "1") (pinfunction "1_1") (pintype "passive"))
      (node (ref "C395") (pin "2") (pinfunction "2_2") (pintype "passive"))
      (node (ref "C397") (pin "1") (pinfunction "1_1") (pintype "passive"))
      (node (ref "C398") (pin "1") (pinfunction "1_1") (pintype "passive"))
      (node (ref "C399") (pin "1") (pinfunction "1_1") (pintype "passive"))
      (node (ref "C400") (pin "1") (pinfunction "1_1") (pintype "passive"))
      (node (ref "C401") (pin "1") (pinfunction "1_1") (pintype "passive"))
      (node (ref "C402") (pin "1") (pinfunction "1_1") (pintype "passive"))
      (node (ref "C403") (pin "1") (pinfunction "1_1") (pintype "passive"))
      (node (ref "C404") (pin "1") (pinfunction "1_1") (pintype "passive"))
      (node (ref "C405") (pin "1") (pinfunction "1_1") (pintype "passive"))
      (node (ref "C406") (pin "2") (pinfunction "2_2") (pintype "passive"))
      (node (ref "C407") (pin "2") (pinfunction "2_2") (pintype "passive"))
      (node (ref "C408") (pin "2") (pinfunction "2_2") (pintype "passive"))
      (node (ref "C409") (pin "2") (pinfunction "2_2") (pintype "passive"))
      (node (ref "C410") (pin "1") (pinfunction "1_1") (pintype "passive"))
      (node (ref "C411") (pin "1") (pinfunction "1_1") (pintype "passive"))
      (node (ref "C412") (pin "1") (pinfunction "1_1") (pintype "passive"))
      (node (ref "C413") (pin "1") (pinfunction "1_1") (pintype "passive"))
      (node (ref "C414") (pin "1") (pinfunction "1_1") (pintype "passive"))
      (node (ref "C415") (pin "1") (pinfunction "1_1") (pintype "passive"))
      (node (ref "C416") (pin "1") (pinfunction "1_1") (pintype "passive"))
      (node (ref "C417") (pin "1") (pinfunction "1_1") (pintype "passive"))
      (node (ref "C418") (pin "1") (pinfunction "1_1") (pintype "passive"))
      (node (ref "C419") (pin "1") (pinfunction "1_1") (pintype "passive"))
      (node (ref "IC21") (pin "4") (pinfunction "GND_4") (pintype "passive"))
      (node (ref "IC21") (pin "9") (pinfunction "PAD_9") (pintype "passive"))
      (node (ref "IC22") (pin "4") (pinfunction "GND_4") (pintype "passive"))
      (node (ref "IC22") (pin "7") (pinfunction "GND_7") (pintype "passive"))
      (node (ref "IC24") (pin "10") (pinfunction "PGND_10") (pintype "passive"))
      (node (ref "IC24") (pin "11") (pinfunction "PGND_11") (pintype "passive"))
      (node (ref "IC24") (pin "12") (pinfunction "PGND_12") (pintype "passive"))
      (node (ref "IC24") (pin "13") (pinfunction "PGND_13") (pintype "passive"))
      (node (ref "IC24") (pin "25") (pinfunction "GND_25") (pintype "passive"))
      (node (ref "IC24") (pin "4") (pinfunction "GND_4") (pintype "passive"))
      (node (ref "IC24") (pin "8") (pinfunction "PGND_8") (pintype "passive"))
      (node (ref "IC24") (pin "9") (pinfunction "PGND_9") (pintype "passive"))
      (node (ref "IC25") (pin "4") (pinfunction "GND_4") (pintype "passive"))
      (node (ref "IC25") (pin "9") (pinfunction "PAD_9") (pintype "passive"))
      (node (ref "IC26") (pin "11") (pinfunction "GND_11") (pintype "passive"))
      (node (ref "IC26") (pin "4") (pinfunction "PGND_4") (pintype "passive"))
      (node (ref "IC26") (pin "8") (pinfunction "GND_8") (pintype "passive"))
      (node (ref "IC27") (pin "4") (pinfunction "GND_4") (pintype "passive"))
      (node (ref "IC27") (pin "9") (pinfunction "PAD_9") (pintype "passive"))
      (node (ref "IC28") (pin "10") (pinfunction "PGND_10") (pintype "passive"))
      (node (ref "IC28") (pin "11") (pinfunction "PGND_11") (pintype "passive"))
      (node (ref "IC28") (pin "12") (pinfunction "PGND_12") (pintype "passive"))
      (node (ref "IC28") (pin "13") (pinfunction "PGND_13") (pintype "passive"))
      (node (ref "IC28") (pin "25") (pinfunction "GND_25") (pintype "passive"))
      (node (ref "IC28") (pin "4") (pinfunction "GND_4") (pintype "passive"))
      (node (ref "IC28") (pin "8") (pinfunction "PGND_8") (pintype "passive"))
      (node (ref "IC28") (pin "9") (pinfunction "PGND_9") (pintype "passive"))
      (node (ref "IC29") (pin "4") (pinfunction "GND_4") (pintype "passive"))
      (node (ref "IC29") (pin "9") (pinfunction "PAD_9") (pintype "passive"))
      (node (ref "IC30") (pin "4") (pinfunction "GND_4") (pintype "passive"))
      (node (ref "IC30") (pin "9") (pinfunction "PAD_9") (pintype "passive"))
      (node (ref "IC31") (pin "3") (pinfunction "GND_3") (pintype "passive"))
      (node (ref "IC32") (pin "4") (pinfunction "GND_4") (pintype "passive"))
      (node (ref "IC32") (pin "9") (pinfunction "PAD_9") (pintype "passive"))
      (node (ref "IC33") (pin "7") (pinfunction "GND_7") (pintype "passive"))
      (node (ref "IC33") (pin "9") (pinfunction "PAD_9") (pintype "passive"))
      (node (ref "J17") (pin "2") (pinfunction "2_2") (pintype "passive"))
      (node (ref "J17") (pin "3") (pinfunction "3_3") (pintype "passive"))
      (node (ref "J18") (pin "1") (pinfunction "1_1") (pintype "passive"))
      (node (ref "LED9") (pin "K") (pinfunction "C_K") (pintype "power_in"))
      (node (ref "MECH11") (pin "MH1") (pinfunction "MH1_MH1") (pintype "passive"))
      (node (ref "MECH12") (pin "MH1") (pinfunction "MH1_MH1") (pintype "passive"))
      (node (ref "MECH13") (pin "MH1") (pinfunction "MH1_MH1") (pintype "passive"))
      (node (ref "MECH14") (pin "MH1") (pinfunction "MH1_MH1") (pintype "passive"))
      (node (ref "R142") (pin "2") (pinfunction "2_2") (pintype "passive"))
      (node (ref "R146") (pin "2") (pinfunction "2_2") (pintype "passive"))
      (node (ref "R148") (pin "1") (pinfunction "1_1") (pintype "passive"))
      (node (ref "R149") (pin "2") (pinfunction "2_2") (pintype "passive"))
      (node (ref "R150") (pin "1") (pinfunction "1_1") (pintype "passive"))
      (node (ref "R156") (pin "1") (pinfunction "1_1") (pintype "passive"))
      (node (ref "R162") (pin "1") (pinfunction "1_1") (pintype "passive"))
      (node (ref "R163") (pin "2") (pinfunction "2_2") (pintype "passive"))
      (node (ref "R164") (pin "2") (pinfunction "2_2") (pintype "passive"))
      (node (ref "R165") (pin "1") (pinfunction "1_1") (pintype "passive"))
      (node (ref "R166") (pin "2") (pinfunction "2_2") (pintype "passive"))
      (node (ref "R172") (pin "2") (pinfunction "2_2") (pintype "passive"))
      (node (ref "R173") (pin "2") (pinfunction "2_2") (pintype "passive"))
      (node (ref "R175") (pin "1") (pinfunction "1_1") (pintype "passive"))
      (node (ref "TP1") (pin "1") (pintype "passive"))
      (node (ref "TP2") (pin "1") (pintype "passive"))
      (node (ref "VD1") (pin "2") (pinfunction "2_2") (pintype "passive"))
    )
    (net (code "2") (name "Net-(C376-Pad2)") (class "Default")
      (node (ref "C376") (pin "2") (pinfunction "2_2") (pintype "passive"))
      (node (ref "IC24") (pin "14") (pinfunction "SW_14") (pintype "passive"))
      (node (ref "IC24") (pin "26") (pinfunction "SW_26") (pintype "passive"))
      (node (ref "IC24") (pin "5") (pinfunction "SW_5") (pintype "passive"))
      (node (ref "IC24") (pin "6") (pinfunction "SW_6") (pintype "passive"))
      (node (ref "IC24") (pin "7") (pinfunction "SW_7") (pintype "passive"))
      (node (ref "L1") (pin "1") (pinfunction "1_1") (pintype "passive"))
    )
    (net (code "3") (name "Net-(C390-Pad1)") (class "Default")
      (node (ref "C390") (pin "1") (pinfunction "1_1") (pintype "passive"))
      (node (ref "R151") (pin "1") (pinfunction "1_1") (pintype "passive"))
    )
    (net (code "4") (name "Net-(C396-Pad2)") (class "Default")
      (node (ref "C396") (pin "2") (pinfunction "2_2") (pintype "passive"))
      (node (ref "IC28") (pin "14") (pinfunction "SW_14") (pintype "passive"))
      (node (ref "IC28") (pin "26") (pinfunction "SW_26") (pintype "passive"))
      (node (ref "IC28") (pin "5") (pinfunction "SW_5") (pintype "passive"))
      (node (ref "IC28") (pin "6") (pinfunction "SW_6") (pintype "passive"))
      (node (ref "IC28") (pin "7") (pinfunction "SW_7") (pintype "passive"))
      (node (ref "L2") (pin "1") (pinfunction "1_1") (pintype "passive"))
    )
    (net (code "5") (name "Net-(C408-Pad1)") (class "Default")
      (node (ref "C408") (pin "1") (pinfunction "1_1") (pintype "passive"))
      (node (ref "R167") (pin "1") (pinfunction "1_1") (pintype "passive"))
    )
    (net (code "6") (name "Net-(IC21-ADJ{slash}NC)") (class "Default")
      (node (ref "IC21") (pin "3") (pinfunction "ADJ/NC_3") (pintype "passive"))
      (node (ref "R141") (pin "1") (pinfunction "1_1") (pintype "passive"))
      (node (ref "R142") (pin "1") (pinfunction "1_1") (pintype "passive"))
    )
    (net (code "7") (name "Net-(IC21-OUT)") (class "Default")
      (node (ref "C374") (pin "2") (pinfunction "2_2") (pintype "passive"))
      (node (ref "IC21") (pin "1") (pinfunction "OUT_1") (pintype "output"))
      (node (ref "R140") (pin "2") (pinfunction "2_2") (pintype "passive"))
      (node (ref "R141") (pin "2") (pinfunction "2_2") (pintype "passive"))
    )
    (net (code "8") (name "Net-(IC22-GATE)") (class "Default")
      (node (ref "IC22") (pin "3") (pinfunction "GATE_3") (pintype "passive"))
      (node (ref "VT7") (pin "4") (pinfunction "G_4") (pintype "passive"))
    )
    (net (code "9") (name "Net-(IC23-GATE)") (class "Default")
      (node (ref "IC23") (pin "3") (pinfunction "GATE_3") (pintype "passive"))
      (node (ref "VT6") (pin "4") (pinfunction "G_4") (pintype "passive"))
    )
    (net (code "10") (name "Net-(IC23-GND-Pad4)") (class "Default")
      (node (ref "IC23") (pin "4") (pinfunction "GND_4") (pintype "passive"))
      (node (ref "IC23") (pin "7") (pinfunction "GND_7") (pintype "passive"))
      (node (ref "VD1") (pin "3") (pinfunction "3_3") (pintype "passive"))
    )
    (net (code "11") (name "Net-(IC23-IN)") (class "Default")
      (node (ref "C372") (pin "1") (pinfunction "1_1") (pintype "passive"))
      (node (ref "IC23") (pin "2") (pinfunction "IN_2") (pintype "passive"))
      (node (ref "J17") (pin "1") (pinfunction "1_1") (pintype "passive"))
      (node (ref "R137") (pin "2") (pinfunction "2_2") (pintype "passive"))
      (node (ref "VD1") (pin "1") (pinfunction "1_1") (pintype "passive"))
      (node (ref "VT6") (pin "1") (pinfunction "S_1") (pintype "passive"))
      (node (ref "VT6") (pin "2") (pinfunction "S_2") (pintype "passive"))
      (node (ref "VT6") (pin "3") (pinfunction "S_3") (pintype "passive"))
    )
    (net (code "12") (name "Net-(IC24-BST)") (class "Default")
      (node (ref "C376") (pin "1") (pinfunction "1_1") (pintype "passive"))
      (node (ref "IC24") (pin "15") (pinfunction "BST_15") (pintype "passive"))
    )
    (net (code "13") (name "Net-(IC24-COMP)") (class "Default")
      (node (ref "C389") (pin "1") (pinfunction "1_1") (pintype "passive"))
      (node (ref "IC24") (pin "1") (pinfunction "COMP_1") (pintype "passive"))
      (node (ref "R151") (pin "2") (pinfunction "2_2") (pintype "passive"))
    )
    (net (code "14") (name "Net-(IC24-FB)") (class "Default")
      (node (ref "IC24") (pin "2") (pinfunction "FB_2") (pintype "passive"))
      (node (ref "R147") (pin "2") (pinfunction "2_2") (pintype "passive"))
      (node (ref "R150") (pin "2") (pinfunction "2_2") (pintype "passive"))
    )
    (net (code "15") (name "Net-(IC24-RT)") (class "Default")
      (node (ref "IC24") (pin "22") (pinfunction "RT_22") (pintype "passive"))
      (node (ref "R149") (pin "1") (pinfunction "1_1") (pintype "passive"))
    )
    (net (code "16") (name "Net-(IC24-SS)") (class "Default")
      (node (ref "C392") (pin "1") (pinfunction "1_1") (pintype "passive"))
      (node (ref "IC24") (pin "24") (pinfunction "SS_24") (pintype "passive"))
    )
    (net (code "17") (name "Net-(IC24-SYNC)") (class "Default")
      (node (ref "IC24") (pin "23") (pinfunction "SYNC_23") (pintype "passive"))
      (node (ref "R148") (pin "2") (pinfunction "2_2") (pintype "passive"))
    )
    (net (code "18") (name "Net-(IC24-VREG)") (class "Default")
      (node (ref "C385") (pin "1") (pinfunction "1_1") (pintype "passive"))
      (node (ref "IC24") (pin "3") (pinfunction "VREG_3") (pintype "passive"))
    )
    (net (code "19") (name "Net-(IC25-ADJ{slash}NC)") (class "Default")
      (node (ref "IC25") (pin "3") (pinfunction "ADJ/NC_3") (pintype "passive"))
      (node (ref "R145") (pin "1") (pinfunction "1_1") (pintype "passive"))
      (node (ref "R146") (pin "1") (pinfunction "1_1") (pintype "passive"))
    )
    (net (code "20") (name "Net-(IC25-EN)") (class "Default")
      (node (ref "C379") (pin "2") (pinfunction "2_2") (pintype "passive"))
      (node (ref "FR51") (pin "2") (pinfunction "2_2") (pintype "passive"))
      (node (ref "IC25") (pin "5") (pinfunction "EN_5") (pintype "input"))
      (node (ref "IC25") (pin "8") (pinfunction "IN_8") (pintype "input"))
    )
    (net (code "21") (name "Net-(IC25-OUT)") (class "Default")
      (node (ref "C380") (pin "2") (pinfunction "2_2") (pintype "passive"))
      (node (ref "IC25") (pin "1") (pinfunction "OUT_1") (pintype "output"))
      (node (ref "R144") (pin "2") (pinfunction "2_2") (pintype "passive"))
      (node (ref "R145") (pin "2") (pinfunction "2_2") (pintype "passive"))
    )
    (net (code "22") (name "Net-(IC26-S3)") (class "Default")
      (node (ref "IC26") (pin "7") (pinfunction "S3_7") (pintype "passive"))
      (node (ref "R154") (pin "2") (pinfunction "2_2") (pintype "passive"))
    )
    (net (code "23") (name "Net-(IC26-S5)") (class "Default")
      (node (ref "IC26") (pin "9") (pinfunction "S5_9") (pintype "passive"))
      (node (ref "R152") (pin "2") (pinfunction "2_2") (pintype "passive"))
    )
    (net (code "24") (name "Net-(IC27-ADJ{slash}NC)") (class "Default")
      (node (ref "IC27") (pin "3") (pinfunction "ADJ/NC_3") (pintype "passive"))
      (node (ref "R155") (pin "2") (pinfunction "2_2") (pintype "passive"))
      (node (ref "R156") (pin "2") (pinfunction "2_2") (pintype "passive"))
    )
    (net (code "25") (name "Net-(IC27-EN)") (class "Default")
      (node (ref "C387") (pin "2") (pinfunction "2_2") (pintype "passive"))
      (node (ref "FR52") (pin "2") (pinfunction "2_2") (pintype "passive"))
      (node (ref "IC27") (pin "5") (pinfunction "EN_5") (pintype "input"))
      (node (ref "IC27") (pin "8") (pinfunction "IN_8") (pintype "input"))
    )
    (net (code "26") (name "Net-(IC27-OUT)") (class "Default")
      (node (ref "C388") (pin "2") (pinfunction "2_2") (pintype "passive"))
      (node (ref "IC27") (pin "1") (pinfunction "OUT_1") (pintype "output"))
      (node (ref "R153") (pin "2") (pinfunction "2_2") (pintype "passive"))
      (node (ref "R155") (pin "1") (pinfunction "1_1") (pintype "passive"))
    )
    (net (code "27") (name "Net-(IC28-BST)") (class "Default")
      (node (ref "C396") (pin "1") (pinfunction "1_1") (pintype "passive"))
      (node (ref "IC28") (pin "15") (pinfunction "BST_15") (pintype "passive"))
    )
    (net (code "28") (name "Net-(IC28-COMP)") (class "Default")
      (node (ref "C407") (pin "1") (pinfunction "1_1") (pintype "passive"))
      (node (ref "IC28") (pin "1") (pinfunction "COMP_1") (pintype "passive"))
      (node (ref "R167") (pin "2") (pinfunction "2_2") (pintype "passive"))
    )
    (net (code "29") (name "Net-(IC28-FB)") (class "Default")
      (node (ref "IC28") (pin "2") (pinfunction "FB_2") (pintype "passive"))
      (node (ref "R161") (pin "2") (pinfunction "2_2") (pintype "passive"))
      (node (ref "R166") (pin "1") (pinfunction "1_1") (pintype "passive"))
    )
    (net (code "30") (name "Net-(IC28-RT)") (class "Default")
      (node (ref "IC28") (pin "22") (pinfunction "RT_22") (pintype "passive"))
      (node (ref "R163") (pin "1") (pinfunction "1_1") (pintype "passive"))
    )
    (net (code "31") (name "Net-(IC28-SS)") (class "Default")
      (node (ref "C409") (pin "1") (pinfunction "1_1") (pintype "passive"))
      (node (ref "IC28") (pin "24") (pinfunction "SS_24") (pintype "passive"))
    )
    (net (code "32") (name "Net-(IC28-SYNC)") (class "Default")
      (node (ref "IC28") (pin "23") (pinfunction "SYNC_23") (pintype "passive"))
      (node (ref "R162") (pin "2") (pinfunction "2_2") (pintype "passive"))
    )
    (net (code "33") (name "Net-(IC28-VREG)") (class "Default")
      (node (ref "C406") (pin "1") (pinfunction "1_1") (pintype "passive"))
      (node (ref "IC28") (pin "3") (pinfunction "VREG_3") (pintype "passive"))
    )
    (net (code "34") (name "Net-(IC29-ADJ{slash}NC)") (class "Default")
      (node (ref "IC29") (pin "3") (pinfunction "ADJ/NC_3") (pintype "passive"))
      (node (ref "R159") (pin "1") (pinfunction "1_1") (pintype "passive"))
      (node (ref "R164") (pin "1") (pinfunction "1_1") (pintype "passive"))
    )
    (net (code "35") (name "Net-(IC29-OUT)") (class "Default")
      (node (ref "C399") (pin "2") (pinfunction "2_2") (pintype "passive"))
      (node (ref "IC29") (pin "1") (pinfunction "OUT_1") (pintype "output"))
      (node (ref "R157") (pin "2") (pinfunction "2_2") (pintype "passive"))
      (node (ref "R159") (pin "2") (pinfunction "2_2") (pintype "passive"))
    )
    (net (code "36") (name "Net-(IC30-ADJ{slash}NC)") (class "Default")
      (node (ref "IC30") (pin "3") (pinfunction "ADJ/NC_3") (pintype "passive"))
      (node (ref "R160") (pin "1") (pinfunction "1_1") (pintype "passive"))
      (node (ref "R165") (pin "2") (pinfunction "2_2") (pintype "passive"))
    )
    (net (code "37") (name "Net-(IC30-EN)") (class "Default")
      (node (ref "C401") (pin "2") (pinfunction "2_2") (pintype "passive"))
      (node (ref "FR53") (pin "2") (pinfunction "2_2") (pintype "passive"))
      (node (ref "IC30") (pin "5") (pinfunction "EN_5") (pintype "input"))
      (node (ref "IC30") (pin "8") (pinfunction "IN_8") (pintype "input"))
    )
    (net (code "38") (name "Net-(IC30-OUT)") (class "Default")
      (node (ref "C402") (pin "2") (pinfunction "2_2") (pintype "passive"))
      (node (ref "IC30") (pin "1") (pinfunction "OUT_1") (pintype "output"))
      (node (ref "R158") (pin "2") (pinfunction "2_2") (pintype "passive"))
      (node (ref "R160") (pin "2") (pinfunction "2_2") (pintype "passive"))
    )
    (net (code "39") (name "Net-(IC31-ADJUST)") (class "Default")
      (node (ref "IC31") (pin "5") (pinfunction "ADJUST_5") (pintype "passive"))
      (node (ref "R170") (pin "2") (pinfunction "2_2") (pintype "passive"))
      (node (ref "R172") (pin "1") (pinfunction "1_1") (pintype "passive"))
    )
    (net (code "40") (name "Net-(IC31-IN)") (class "Default")
      (node (ref "C412") (pin "2") (pinfunction "2_2") (pintype "passive"))
      (node (ref "FR54") (pin "2") (pinfunction "2_2") (pintype "passive"))
      (node (ref "IC31") (pin "2") (pinfunction "IN_2") (pintype "passive"))
    )
    (net (code "41") (name "Net-(IC31-OUT)") (class "Default")
      (node (ref "C411") (pin "2") (pinfunction "2_2") (pintype "passive"))
      (node (ref "IC31") (pin "4") (pinfunction "OUT_4") (pintype "passive"))
      (node (ref "R168") (pin "2") (pinfunction "2_2") (pintype "passive"))
      (node (ref "R170") (pin "1") (pinfunction "1_1") (pintype "passive"))
    )
    (net (code "42") (name "Net-(IC32-ADJ{slash}NC)") (class "Default")
      (node (ref "IC32") (pin "3") (pinfunction "ADJ/NC_3") (pintype "passive"))
      (node (ref "R171") (pin "1") (pinfunction "1_1") (pintype "passive"))
      (node (ref "R173") (pin "1") (pinfunction "1_1") (pintype "passive"))
    )
    (net (code "43") (name "Net-(IC32-OUT)") (class "Default")
      (node (ref "C414") (pin "2") (pinfunction "2_2") (pintype "passive"))
      (node (ref "IC32") (pin "1") (pinfunction "OUT_1") (pintype "output"))
      (node (ref "R169") (pin "2") (pinfunction "2_2") (pintype "passive"))
      (node (ref "R171") (pin "2") (pinfunction "2_2") (pintype "passive"))
    )
    (net (code "44") (name "Net-(IC33-ADJ{slash}BYP)") (class "Default")
      (node (ref "IC33") (pin "8") (pinfunction "ADJ/BYP_8") (pintype "input"))
      (node (ref "R174") (pin "2") (pinfunction "2_2") (pintype "passive"))
      (node (ref "R175") (pin "2") (pinfunction "2_2") (pintype "passive"))
    )
    (net (code "45") (name "Net-(IC33-EN)") (class "Default")
      (node (ref "C419") (pin "2") (pinfunction "2_2") (pintype "passive"))
      (node (ref "IC33") (pin "1") (pinfunction "EN_1") (pintype "input"))
      (node (ref "R176") (pin "2") (pinfunction "2_2") (pintype "passive"))
      (node (ref "R177") (pin "1") (pinfunction "1_1") (pintype "passive"))
    )
    (net (code "46") (name "Net-(IC33-VIN)") (class "Default")
      (node (ref "C418") (pin "2") (pinfunction "2_2") (pintype "passive"))
      (node (ref "FR55") (pin "2") (pinfunction "2_2") (pintype "passive"))
      (node (ref "IC33") (pin "3") (pinfunction "VIN_3") (pintype "input"))
    )
    (net (code "47") (name "Net-(IC33-VOUT)") (class "Default")
      (node (ref "C415") (pin "2") (pinfunction "2_2") (pintype "passive"))
      (node (ref "FR56") (pin "1") (pinfunction "1_1") (pintype "passive"))
      (node (ref "IC33") (pin "5") (pinfunction "VOUT_5") (pintype "output"))
      (node (ref "R174") (pin "1") (pinfunction "1_1") (pintype "passive"))
    )
    (net (code "48") (name "Net-(LED9-PadA)") (class "Default")
      (node (ref "LED9") (pin "A") (pinfunction "A_A") (pintype "power_in"))
      (node (ref "R143") (pin "1") (pinfunction "1_1") (pintype "passive"))
    )
    (net (code "49") (name "VCC1P2") (class "Default")
      (node (ref "C403") (pin "2") (pinfunction "2_2") (pintype "passive"))
      (node (ref "C404") (pin "2") (pinfunction "2_2") (pintype "passive"))
      (node (ref "C405") (pin "2") (pinfunction "2_2") (pintype "passive"))
      (node (ref "L2") (pin "2") (pinfunction "2_2") (pintype "passive"))
      (node (ref "R161") (pin "1") (pinfunction "1_1") (pintype "passive"))
    )
    (net (code "50") (name "VCC1P4_LMS") (class "Default")
      (node (ref "R153") (pin "1") (pinfunction "1_1") (pintype "passive"))
    )
    (net (code "51") (name "VCC1P8") (class "Default")
      (node (ref "R169") (pin "1") (pinfunction "1_1") (pintype "passive"))
    )
    (net (code "52") (name "VCC1P8_DDR2") (class "Default")
      (node (ref "C384") (pin "2") (pinfunction "2_2") (pintype "passive"))
      (node (ref "IC26") (pin "1") (pinfunction "VDDQSNS_1") (pintype "passive"))
      (node (ref "IC26") (pin "2") (pinfunction "VLDOIN_2") (pintype "passive"))
      (node (ref "R157") (pin "1") (pinfunction "1_1") (pintype "passive"))
    )
    (net (code "53") (name "VCC1P8_LMS") (class "Default")
      (node (ref "R144") (pin "1") (pinfunction "1_1") (pintype "passive"))
    )
    (net (code "54") (name "VCC1P25_LMS") (class "Default")
      (node (ref "R158") (pin "1") (pinfunction "1_1") (pintype "passive"))
    )
    (net (code "55") (name "VCC1P25_LMS_DIG") (class "Default")
      (node (ref "R168") (pin "1") (pinfunction "1_1") (pintype "passive"))
    )
    (net (code "56") (name "VCC2P5") (class "Default")
      (node (ref "R139") (pin "2") (pinfunction "2_2") (pintype "passive"))
      (node (ref "R140") (pin "1") (pinfunction "1_1") (pintype "passive"))
    )
    (net (code "57") (name "VCC3P3") (class "Default")
      (node (ref "C373") (pin "2") (pinfunction "2_2") (pintype "passive"))
      (node (ref "C378") (pin "2") (pinfunction "2_2") (pintype "passive"))
      (node (ref "C381") (pin "2") (pinfunction "2_2") (pintype "passive"))
      (node (ref "C382") (pin "2") (pinfunction "2_2") (pintype "passive"))
      (node (ref "C383") (pin "2") (pinfunction "2_2") (pintype "passive"))
      (node (ref "C386") (pin "2") (pinfunction "2_2") (pintype "passive"))
      (node (ref "C391") (pin "2") (pinfunction "2_2") (pintype "passive"))
      (node (ref "C398") (pin "2") (pinfunction "2_2") (pintype "passive"))
      (node (ref "C400") (pin "2") (pinfunction "2_2") (pintype "passive"))
      (node (ref "C410") (pin "2") (pinfunction "2_2") (pintype "passive"))
      (node (ref "C413") (pin "2") (pinfunction "2_2") (pintype "passive"))
      (node (ref "FR51") (pin "1") (pinfunction "1_1") (pintype "passive"))
      (node (ref "FR52") (pin "1") (pinfunction "1_1") (pintype "passive"))
      (node (ref "FR53") (pin "1") (pinfunction "1_1") (pintype "passive"))
      (node (ref "FR54") (pin "1") (pinfunction "1_1") (pintype "passive"))
      (node (ref "IC21") (pin "5") (pinfunction "EN_5") (pintype "input"))
      (node (ref "IC21") (pin "8") (pinfunction "IN_8") (pintype "input"))
      (node (ref "IC26") (pin "10") (pinfunction "VIN_10") (pintype "passive"))
      (node (ref "IC29") (pin "5") (pinfunction "EN_5") (pintype "input"))
      (node (ref "IC29") (pin "8") (pinfunction "IN_8") (pintype "input"))
      (node (ref "IC32") (pin "5") (pinfunction "EN_5") (pintype "input"))
      (node (ref "IC32") (pin "8") (pinfunction "IN_8") (pintype "input"))
      (node (ref "L1") (pin "2") (pinfunction "2_2") (pintype "passive"))
      (node (ref "R136") (pin "2") (pinfunction "2_2") (pintype "passive"))
      (node (ref "R143") (pin "2") (pinfunction "2_2") (pintype "passive"))
      (node (ref "R147") (pin "1") (pinfunction "1_1") (pintype "passive"))
      (node (ref "R152") (pin "1") (pinfunction "1_1") (pintype "passive"))
      (node (ref "R154") (pin "1") (pinfunction "1_1") (pintype "passive"))
    )
    (net (code "58") (name "VCC3P3_CLK") (class "Default")
      (node (ref "C416") (pin "2") (pinfunction "2_2") (pintype "passive"))
      (node (ref "FR56") (pin "2") (pinfunction "2_2") (pintype "passive"))
    )
    (net (code "59") (name "VCC12P0") (class "Default")
      (node (ref "C366") (pin "2") (pinfunction "2_2") (pintype "passive"))
      (node (ref "C367") (pin "2") (pinfunction "2_2") (pintype "passive"))
      (node (ref "C368") (pin "2") (pinfunction "2_2") (pintype "passive"))
      (node (ref "C369") (pin "2") (pinfunction "2_2") (pintype "passive"))
      (node (ref "C370") (pin "2") (pinfunction "2_2") (pintype "passive"))
      (node (ref "C371") (pin "1") (pinfunction "1_1") (pintype "passive"))
      (node (ref "C375") (pin "1") (pinfunction "1_1") (pintype "passive"))
      (node (ref "C377") (pin "2") (pinfunction "2_2") (pintype "passive"))
      (node (ref "C397") (pin "2") (pinfunction "2_2") (pintype "passive"))
      (node (ref "C417") (pin "2") (pinfunction "2_2") (pintype "passive"))
      (node (ref "FR55") (pin "1") (pinfunction "1_1") (pintype "passive"))
      (node (ref "IC22") (pin "1") (pinfunction "OUT_1") (pintype "passive"))
      (node (ref "IC22") (pin "6") (pinfunction "VDD_6") (pintype "passive"))
      (node (ref "IC23") (pin "1") (pinfunction "OUT_1") (pintype "passive"))
      (node (ref "IC23") (pin "6") (pinfunction "VDD_6") (pintype "passive"))
      (node (ref "IC24") (pin "16") (pinfunction "PVIN_16") (pintype "passive"))
      (node (ref "IC24") (pin "17") (pinfunction "PVIN_17") (pintype "passive"))
      (node (ref "IC24") (pin "18") (pinfunction "PVIN_18") (pintype "passive"))
      (node (ref "IC24") (pin "19") (pinfunction "PVIN_19") (pintype "passive"))
      (node (ref "IC24") (pin "20") (pinfunction "EN_20") (pintype "passive"))
      (node (ref "IC28") (pin "16") (pinfunction "PVIN_16") (pintype "passive"))
      (node (ref "IC28") (pin "17") (pinfunction "PVIN_17") (pintype "passive"))
      (node (ref "IC28") (pin "18") (pinfunction "PVIN_18") (pintype "passive"))
      (node (ref "IC28") (pin "19") (pinfunction "PVIN_19") (pintype "passive"))
      (node (ref "IC28") (pin "20") (pinfunction "EN_20") (pintype "passive"))
      (node (ref "J18") (pin "2") (pinfunction "2_2") (pintype "passive"))
      (node (ref "R137") (pin "1") (pinfunction "1_1") (pintype "passive"))
      (node (ref "R138") (pin "1") (pinfunction "1_1") (pintype "passive"))
      (node (ref "R177") (pin "2") (pinfunction "2_2") (pintype "passive"))
      (node (ref "VT6") (pin "5") (pinfunction "D_5") (pintype "passive"))
      (node (ref "VT6") (pin "6") (pinfunction "D_6") (pintype "passive"))
      (node (ref "VT6") (pin "7") (pinfunction "D_7") (pintype "passive"))
      (node (ref "VT6") (pin "8") (pinfunction "D_8") (pintype "passive"))
      (node (ref "VT7") (pin "5") (pinfunction "D_5") (pintype "passive"))
      (node (ref "VT7") (pin "6") (pinfunction "D_6") (pintype "passive"))
      (node (ref "VT7") (pin "7") (pinfunction "D_7") (pintype "passive"))
      (node (ref "VT7") (pin "8") (pinfunction "D_8") (pintype "passive"))
    )
    (net (code "60") (name "VCC12P0_PCIE") (class "Default")
      (node (ref "IC22") (pin "2") (pinfunction "IN_2") (pintype "passive"))
      (node (ref "R138") (pin "2") (pinfunction "2_2") (pintype "passive"))
      (node (ref "VT7") (pin "1") (pinfunction "S_1") (pintype "passive"))
      (node (ref "VT7") (pin "2") (pinfunction "S_2") (pintype "passive"))
      (node (ref "VT7") (pin "3") (pinfunction "S_3") (pintype "passive"))
    )
    (net (code "61") (name "VDIO_LMS") (class "Default")
      (node (ref "C364") (pin "2") (pinfunction "2_2") (pintype "passive"))
      (node (ref "C365") (pin "1") (pinfunction "1_1") (pintype "passive"))
      (node (ref "FR50") (pin "2") (pinfunction "2_2") (pintype "passive"))
    )
    (net (code "62") (name "VDIO_LMS_FPGA") (class "Default")
      (node (ref "FR50") (pin "1") (pinfunction "1_1") (pintype "passive"))
      (node (ref "R136") (pin "1") (pinfunction "1_1") (pintype "passive"))
      (node (ref "R139") (pin "1") (pinfunction "1_1") (pintype "passive"))
      (node (ref "R176") (pin "1") (pinfunction "1_1") (pintype "passive"))
    )
    (net (code "63") (name "VREF_DDR2") (class "Default")
      (node (ref "C395") (pin "1") (pinfunction "1_1") (pintype "passive"))
      (node (ref "IC26") (pin "6") (pinfunction "VTTREF_6") (pintype "passive"))
    )
    (net (code "64") (name "VTT_DDR2") (class "Default")
      (node (ref "C393") (pin "2") (pinfunction "2_2") (pintype "passive"))
      (node (ref "C394") (pin "2") (pinfunction "2_2") (pintype "passive"))
      (node (ref "IC26") (pin "3") (pinfunction "VTT_3") (pintype "passive"))
      (node (ref "IC26") (pin "5") (pinfunction "VTTSNS_5") (pintype "passive"))
    )
    (net (code "65") (name "unconnected-(F1-Pad1)") (class "Default")
      (node (ref "F1") (pin "1") (pintype "passive+no_connect"))
    )
    (net (code "66") (name "unconnected-(F2-Pad1)") (class "Default")
      (node (ref "F2") (pin "1") (pintype "passive+no_connect"))
    )
    (net (code "67") (name "unconnected-(F3-Pad1)") (class "Default")
      (node (ref "F3") (pin "1") (pintype "passive+no_connect"))
    )
    (net (code "68") (name "unconnected-(F4-Pad1)") (class "Default")
      (node (ref "F4") (pin "1") (pintype "passive+no_connect"))
    )
    (net (code "69") (name "unconnected-(IC21-NC-Pad2)") (class "Default")
      (node (ref "IC21") (pin "2") (pinfunction "NC_2") (pintype "passive+no_connect"))
    )
    (net (code "70") (name "unconnected-(IC21-NC-Pad6)") (class "Default")
      (node (ref "IC21") (pin "6") (pinfunction "NC_6") (pintype "passive+no_connect"))
    )
    (net (code "71") (name "unconnected-(IC21-NC-Pad7)") (class "Default")
      (node (ref "IC21") (pin "7") (pinfunction "NC_7") (pintype "passive+no_connect"))
    )
    (net (code "72") (name "unconnected-(IC22-NC-Pad5)") (class "Default")
      (node (ref "IC22") (pin "5") (pinfunction "NC_5") (pintype "passive+no_connect"))
    )
    (net (code "73") (name "unconnected-(IC23-NC-Pad5)") (class "Default")
      (node (ref "IC23") (pin "5") (pinfunction "NC_5") (pintype "passive+no_connect"))
    )
    (net (code "74") (name "unconnected-(IC24-PGOOD-Pad21)") (class "Default")
      (node (ref "IC24") (pin "21") (pinfunction "PGOOD_21") (pintype "passive+no_connect"))
    )
    (net (code "75") (name "unconnected-(IC25-NC-Pad2)") (class "Default")
      (node (ref "IC25") (pin "2") (pinfunction "NC_2") (pintype "passive+no_connect"))
    )
    (net (code "76") (name "unconnected-(IC25-NC-Pad6)") (class "Default")
      (node (ref "IC25") (pin "6") (pinfunction "NC_6") (pintype "passive+no_connect"))
    )
    (net (code "77") (name "unconnected-(IC25-NC-Pad7)") (class "Default")
      (node (ref "IC25") (pin "7") (pinfunction "NC_7") (pintype "passive+no_connect"))
    )
    (net (code "78") (name "unconnected-(IC27-NC-Pad2)") (class "Default")
      (node (ref "IC27") (pin "2") (pinfunction "NC_2") (pintype "passive+no_connect"))
    )
    (net (code "79") (name "unconnected-(IC27-NC-Pad6)") (class "Default")
      (node (ref "IC27") (pin "6") (pinfunction "NC_6") (pintype "passive+no_connect"))
    )
    (net (code "80") (name "unconnected-(IC27-NC-Pad7)") (class "Default")
      (node (ref "IC27") (pin "7") (pinfunction "NC_7") (pintype "passive+no_connect"))
    )
    (net (code "81") (name "unconnected-(IC28-PGOOD-Pad21)") (class "Default")
      (node (ref "IC28") (pin "21") (pinfunction "PGOOD_21") (pintype "passive+no_connect"))
    )
    (net (code "82") (name "unconnected-(IC29-NC-Pad2)") (class "Default")
      (node (ref "IC29") (pin "2") (pinfunction "NC_2") (pintype "passive+no_connect"))
    )
    (net (code "83") (name "unconnected-(IC29-NC-Pad6)") (class "Default")
      (node (ref "IC29") (pin "6") (pinfunction "NC_6") (pintype "passive+no_connect"))
    )
    (net (code "84") (name "unconnected-(IC29-NC-Pad7)") (class "Default")
      (node (ref "IC29") (pin "7") (pinfunction "NC_7") (pintype "passive+no_connect"))
    )
    (net (code "85") (name "unconnected-(IC30-NC-Pad2)") (class "Default")
      (node (ref "IC30") (pin "2") (pinfunction "NC_2") (pintype "passive+no_connect"))
    )
    (net (code "86") (name "unconnected-(IC30-NC-Pad6)") (class "Default")
      (node (ref "IC30") (pin "6") (pinfunction "NC_6") (pintype "passive+no_connect"))
    )
    (net (code "87") (name "unconnected-(IC30-NC-Pad7)") (class "Default")
      (node (ref "IC30") (pin "7") (pinfunction "NC_7") (pintype "passive+no_connect"))
    )
    (net (code "88") (name "unconnected-(IC31-NC-Pad1)") (class "Default")
      (node (ref "IC31") (pin "1") (pinfunction "NC_1") (pintype "passive+no_connect"))
    )
    (net (code "89") (name "unconnected-(IC32-NC-Pad2)") (class "Default")
      (node (ref "IC32") (pin "2") (pinfunction "NC_2") (pintype "passive+no_connect"))
    )
    (net (code "90") (name "unconnected-(IC32-NC-Pad6)") (class "Default")
      (node (ref "IC32") (pin "6") (pinfunction "NC_6") (pintype "passive+no_connect"))
    )
    (net (code "91") (name "unconnected-(IC32-NC-Pad7)") (class "Default")
      (node (ref "IC32") (pin "7") (pinfunction "NC_7") (pintype "passive+no_connect"))
    )
    (net (code "92") (name "unconnected-(IC33-NC-Pad2)") (class "Default")
      (node (ref "IC33") (pin "2") (pinfunction "NC_2") (pintype "passive+no_connect"))
    )
    (net (code "93") (name "unconnected-(IC33-NC-Pad4)") (class "Default")
      (node (ref "IC33") (pin "4") (pinfunction "NC_4") (pintype "passive+no_connect"))
    )
    (net (code "94") (name "unconnected-(IC33-NC-Pad6)") (class "Default")
      (node (ref "IC33") (pin "6") (pinfunction "NC_6") (pintype "passive+no_connect"))
    )
  )
)
